# ControladorPOE.net
KiCad netlist of a schematic drawn in Altium Designer
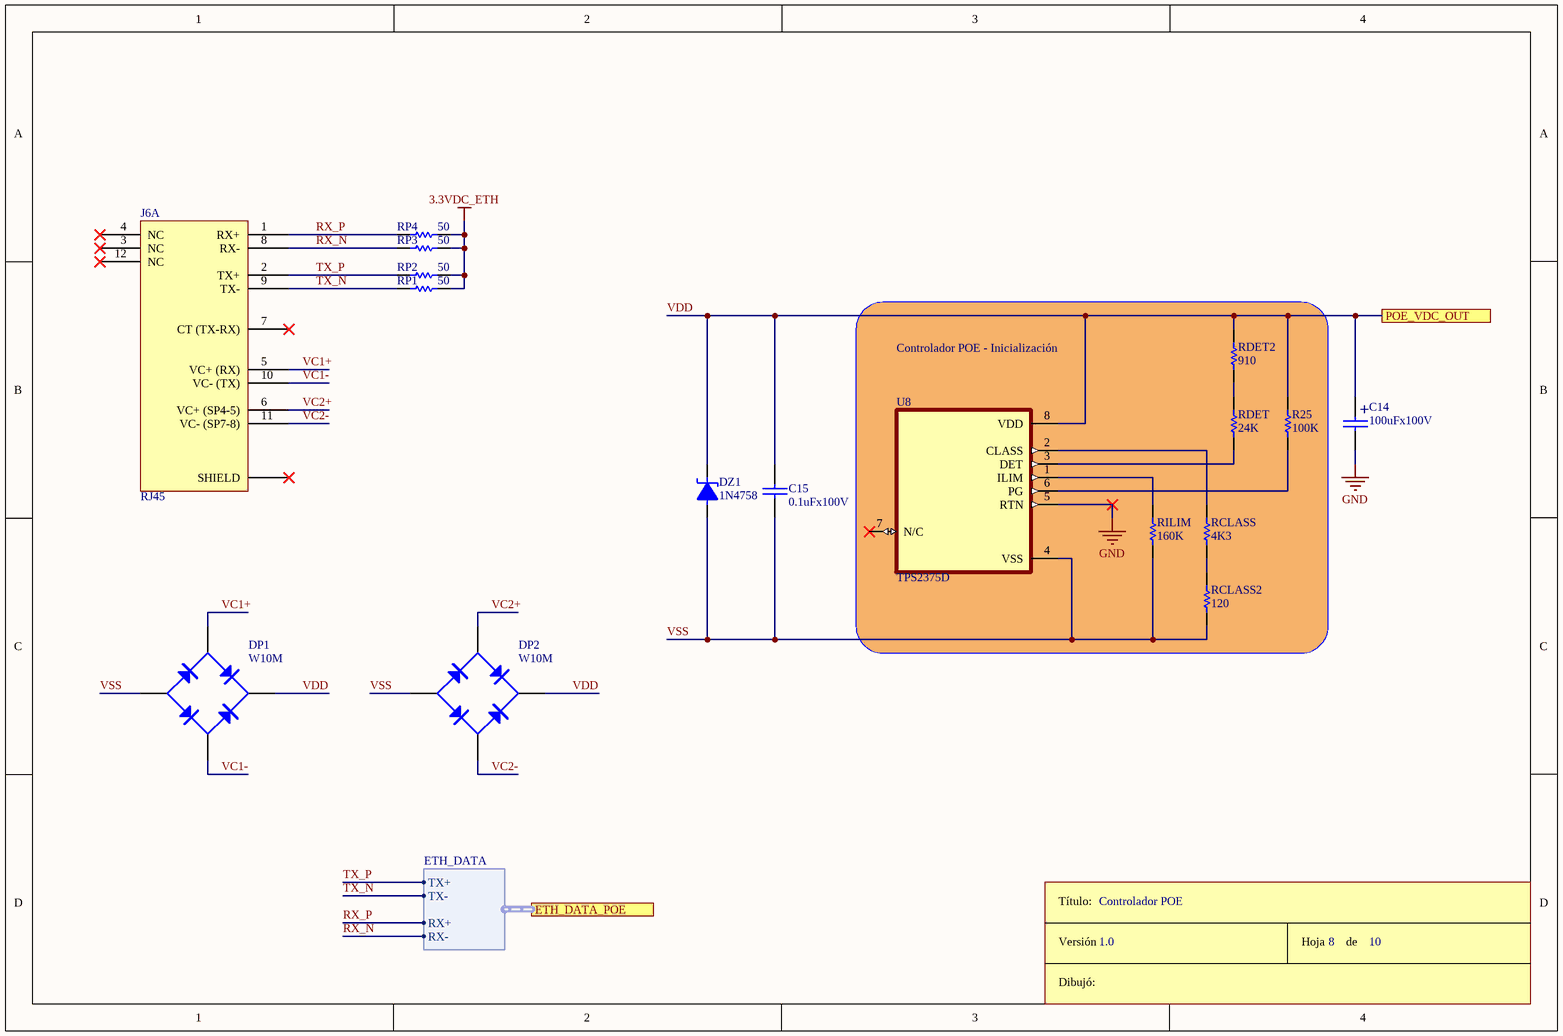
[diagram p0: ControladorPOE.SchDoc]

(export (version "E")
  (design (tool "Eeschema 10.0.6"))
  (components
    (comp (ref "C14")
      (value "100uFx100V")
      (footprint "CAP200RP")
      (libsource (lib "AditionalComponents") (part "CAPPOL"))
    )
    (comp (ref "C15")
      (value "0.1uFx100V")
      (footprint "CAP300v2")
      (libsource (lib "AditionalComponents") (part "CAP"))
    )
    (comp (ref "DP1")
      (value "W10M")
      (footprint "PUENTE - W10M")
      (description "Bridge Rectifier TH 1000V 1.5A")
      (libsource (lib "AditionalComponents") (part "W10M"))
    )
    (comp (ref "DP2")
      (value "W10M")
      (footprint "PUENTE - W10M")
      (description "Bridge Rectifier TH 1000V 1.5A")
      (libsource (lib "AditionalComponents") (part "W10M"))
    )
    (comp (ref "DZ1") (value "1N4758") (footprint "DO41") (libsource (lib "LIBEBAL") (part "DIODO ZENER")))
    (comp (ref "J6A")
      (value "RJ45")
      (footprint "ARJP11C-MB")
      (description "Magjack Connector for PoE")
      (libsource (lib "AditionalComponents") (part "ARJP11C-MBSC-L2"))
    )
    (comp (ref "R25") (value "100K") (footprint "RES300") (libsource (lib "LIBEBAL") (part "RES")))
    (comp (ref "RCLASS") (value "4K3") (footprint "RES300") (libsource (lib "LIBEBAL") (part "RES")))
    (comp (ref "RCLASS2") (value "120") (footprint "RES300") (libsource (lib "LIBEBAL") (part "RES")))
    (comp (ref "RDET") (value "24K") (footprint "RES300") (libsource (lib "LIBEBAL") (part "RES")))
    (comp (ref "RDET2") (value "910") (footprint "RES300") (libsource (lib "LIBEBAL") (part "RES")))
    (comp (ref "RILIM") (value "160K") (footprint "RES300") (libsource (lib "LIBEBAL") (part "RES")))
    (comp (ref "ROT7") (value "Rótulo") (libsource (lib "LIB PIO IX") (part "Rótulo")))
    (comp (ref "RP1") (value "50") (footprint "RES300") (libsource (lib "LIBEBAL") (part "RES")))
    (comp (ref "RP2") (value "50") (footprint "RES300") (libsource (lib "LIBEBAL") (part "RES")))
    (comp (ref "RP3") (value "50") (footprint "RES300") (libsource (lib "LIBEBAL") (part "RES")))
    (comp (ref "RP4") (value "50") (footprint "RES300") (libsource (lib "LIBEBAL") (part "RES")))
    (comp (ref "U8")
      (value "TPS2375D")
      (footprint "SOIC127P599X175-8N")
      (description "Class 3 PoE PD with latch protection 8-SOIC -40 to 85")
      (fields (field (name "DIGI-KEY_PART_NUMBER") "296-26922-2-ND") (field (name "MF") "Texas Instruments"))
      (libsource (lib "TPS2375D_Rev2") (part "TPS2375D"))
    )
  )
  (nets
    (net (code "2") (name "/RX_N") (class "Default")
      (node (ref "J6A") (pin "8") (pinfunction "RX-_8") (pintype "passive"))
      (node (ref "RP3") (pin "1") (pinfunction "1_1") (pintype "passive"))
    )
    (net (code "3") (name "/RX_P") (class "Default")
      (node (ref "J6A") (pin "1") (pinfunction "RX+_1") (pintype "passive"))
      (node (ref "RP4") (pin "1") (pinfunction "1_1") (pintype "passive"))
    )
    (net (code "4") (name "/TX_N") (class "Default")
      (node (ref "J6A") (pin "9") (pinfunction "TX-_9") (pintype "passive"))
      (node (ref "RP1") (pin "1") (pinfunction "1_1") (pintype "passive"))
    )
    (net (code "5") (name "/TX_P") (class "Default")
      (node (ref "J6A") (pin "2") (pinfunction "TX+_2") (pintype "passive"))
      (node (ref "RP2") (pin "1") (pinfunction "1_1") (pintype "passive"))
    )
    (net (code "6") (name "/VC1+") (class "Default")
      (node (ref "DP1") (pin "2") (pinfunction "AC_2") (pintype "passive"))
      (node (ref "J6A") (pin "5") (pinfunction "VC+_(RX)_5") (pintype "passive"))
    )
    (net (code "7") (name "/VC1-") (class "Default")
      (node (ref "DP1") (pin "4") (pinfunction "AC_4") (pintype "passive"))
      (node (ref "J6A") (pin "10") (pinfunction "VC-_(TX)_10") (pintype "passive"))
    )
    (net (code "8") (name "/VC2+") (class "Default")
      (node (ref "DP2") (pin "2") (pinfunction "AC_2") (pintype "passive"))
      (node (ref "J6A") (pin "6") (pinfunction "VC+_(SP4-5)_6") (pintype "passive"))
    )
    (net (code "9") (name "/VC2-") (class "Default")
      (node (ref "DP2") (pin "4") (pinfunction "AC_4") (pintype "passive"))
      (node (ref "J6A") (pin "11") (pinfunction "VC-_(SP7-8)_11") (pintype "passive"))
    )
    (net (code "10") (name "/VDD") (class "Default")
      (node (ref "C14") (pin "1") (pinfunction "1_1") (pintype "passive"))
      (node (ref "C15") (pin "1") (pinfunction "1_1") (pintype "passive"))
      (node (ref "DP1") (pin "1") (pinfunction "V+_1") (pintype "passive"))
      (node (ref "DP2") (pin "1") (pinfunction "V+_1") (pintype "passive"))
      (node (ref "DZ1") (pin "2") (pinfunction "2_2") (pintype "passive"))
      (node (ref "R25") (pin "2") (pinfunction "2_2") (pintype "passive"))
      (node (ref "RDET2") (pin "2") (pinfunction "2_2") (pintype "passive"))
      (node (ref "U8") (pin "8") (pinfunction "VDD_8") (pintype "power_in"))
    )
    (net (code "11") (name "/VSS") (class "Default")
      (node (ref "C15") (pin "2") (pinfunction "2_2") (pintype "passive"))
      (node (ref "DP1") (pin "3") (pinfunction "V-_3") (pintype "passive"))
      (node (ref "DP2") (pin "3") (pinfunction "V-_3") (pintype "passive"))
      (node (ref "DZ1") (pin "1") (pinfunction "1_1") (pintype "passive"))
      (node (ref "RCLASS2") (pin "1") (pinfunction "1_1") (pintype "passive"))
      (node (ref "RILIM") (pin "1") (pinfunction "1_1") (pintype "passive"))
      (node (ref "U8") (pin "4") (pinfunction "VSS_4") (pintype "power_in"))
    )
    (net (code "13") (name "3.3VDC_ETH") (class "Default")
      (node (ref "RP1") (pin "2") (pinfunction "2_2") (pintype "passive"))
      (node (ref "RP2") (pin "2") (pinfunction "2_2") (pintype "passive"))
      (node (ref "RP3") (pin "2") (pinfunction "2_2") (pintype "passive"))
      (node (ref "RP4") (pin "2") (pinfunction "2_2") (pintype "passive"))
    )
    (net (code "14") (name "GND") (class "Default")
      (node (ref "C14") (pin "2") (pinfunction "2_2") (pintype "passive"))
      (node (ref "U8") (pin "5") (pinfunction "RTN_5") (pintype "output"))
    )
    (net (code "15") (name "Net-(RCLASS-Pad1)") (class "Default")
      (node (ref "RCLASS") (pin "1") (pinfunction "1_1") (pintype "passive"))
      (node (ref "RCLASS2") (pin "2") (pinfunction "2_2") (pintype "passive"))
    )
    (net (code "16") (name "Net-(RDET-Pad2)") (class "Default")
      (node (ref "RDET") (pin "2") (pinfunction "2_2") (pintype "passive"))
      (node (ref "RDET2") (pin "1") (pinfunction "1_1") (pintype "passive"))
    )
    (net (code "17") (name "Net-(U8-CLASS)") (class "Default")
      (node (ref "RCLASS") (pin "2") (pinfunction "2_2") (pintype "passive"))
      (node (ref "U8") (pin "2") (pinfunction "CLASS_2") (pintype "output"))
    )
    (net (code "18") (name "Net-(U8-DET)") (class "Default")
      (node (ref "RDET") (pin "1") (pinfunction "1_1") (pintype "passive"))
      (node (ref "U8") (pin "3") (pinfunction "DET_3") (pintype "output"))
    )
    (net (code "19") (name "Net-(U8-ILIM)") (class "Default")
      (node (ref "RILIM") (pin "2") (pinfunction "2_2") (pintype "passive"))
      (node (ref "U8") (pin "1") (pinfunction "ILIM_1") (pintype "output"))
    )
    (net (code "20") (name "Net-(U8-PG)") (class "Default")
      (node (ref "R25") (pin "1") (pinfunction "1_1") (pintype "passive"))
      (node (ref "U8") (pin "6") (pinfunction "PG_6") (pintype "output"))
    )
    (net (code "21") (name "unconnected-(J6A-CT_(TX-RX)-Pad7)") (class "Default")
      (node (ref "J6A") (pin "7") (pinfunction "CT_(TX-RX)_7") (pintype "passive+no_connect"))
    )
    (net (code "22") (name "unconnected-(J6A-NC-Pad3)") (class "Default")
      (node (ref "J6A") (pin "3") (pinfunction "NC_3") (pintype "passive+no_connect"))
    )
    (net (code "23") (name "unconnected-(J6A-NC-Pad4)") (class "Default")
      (node (ref "J6A") (pin "4") (pinfunction "NC_4") (pintype "passive+no_connect"))
    )
    (net (code "24") (name "unconnected-(J6A-NC-Pad12)") (class "Default")
      (node (ref "J6A") (pin "12") (pinfunction "NC_12") (pintype "passive+no_connect"))
    )
    (net (code "25") (name "unconnected-(J6A-PadSHIELD)") (class "Default")
      (node (ref "J6A") (pin "SHIELD") (pinfunction "SHIELD_SHIELD") (pintype "passive+no_connect"))
    )
    (net (code "26") (name "unconnected-(U8-N{slash}C-Pad7)") (class "Default")
      (node (ref "U8") (pin "7") (pinfunction "N/C_7") (pintype "bidirectional+no_connect"))
    )
  )
)
